# Hypnos_V0.net
KiCad netlist of a schematic drawn in EAGLE
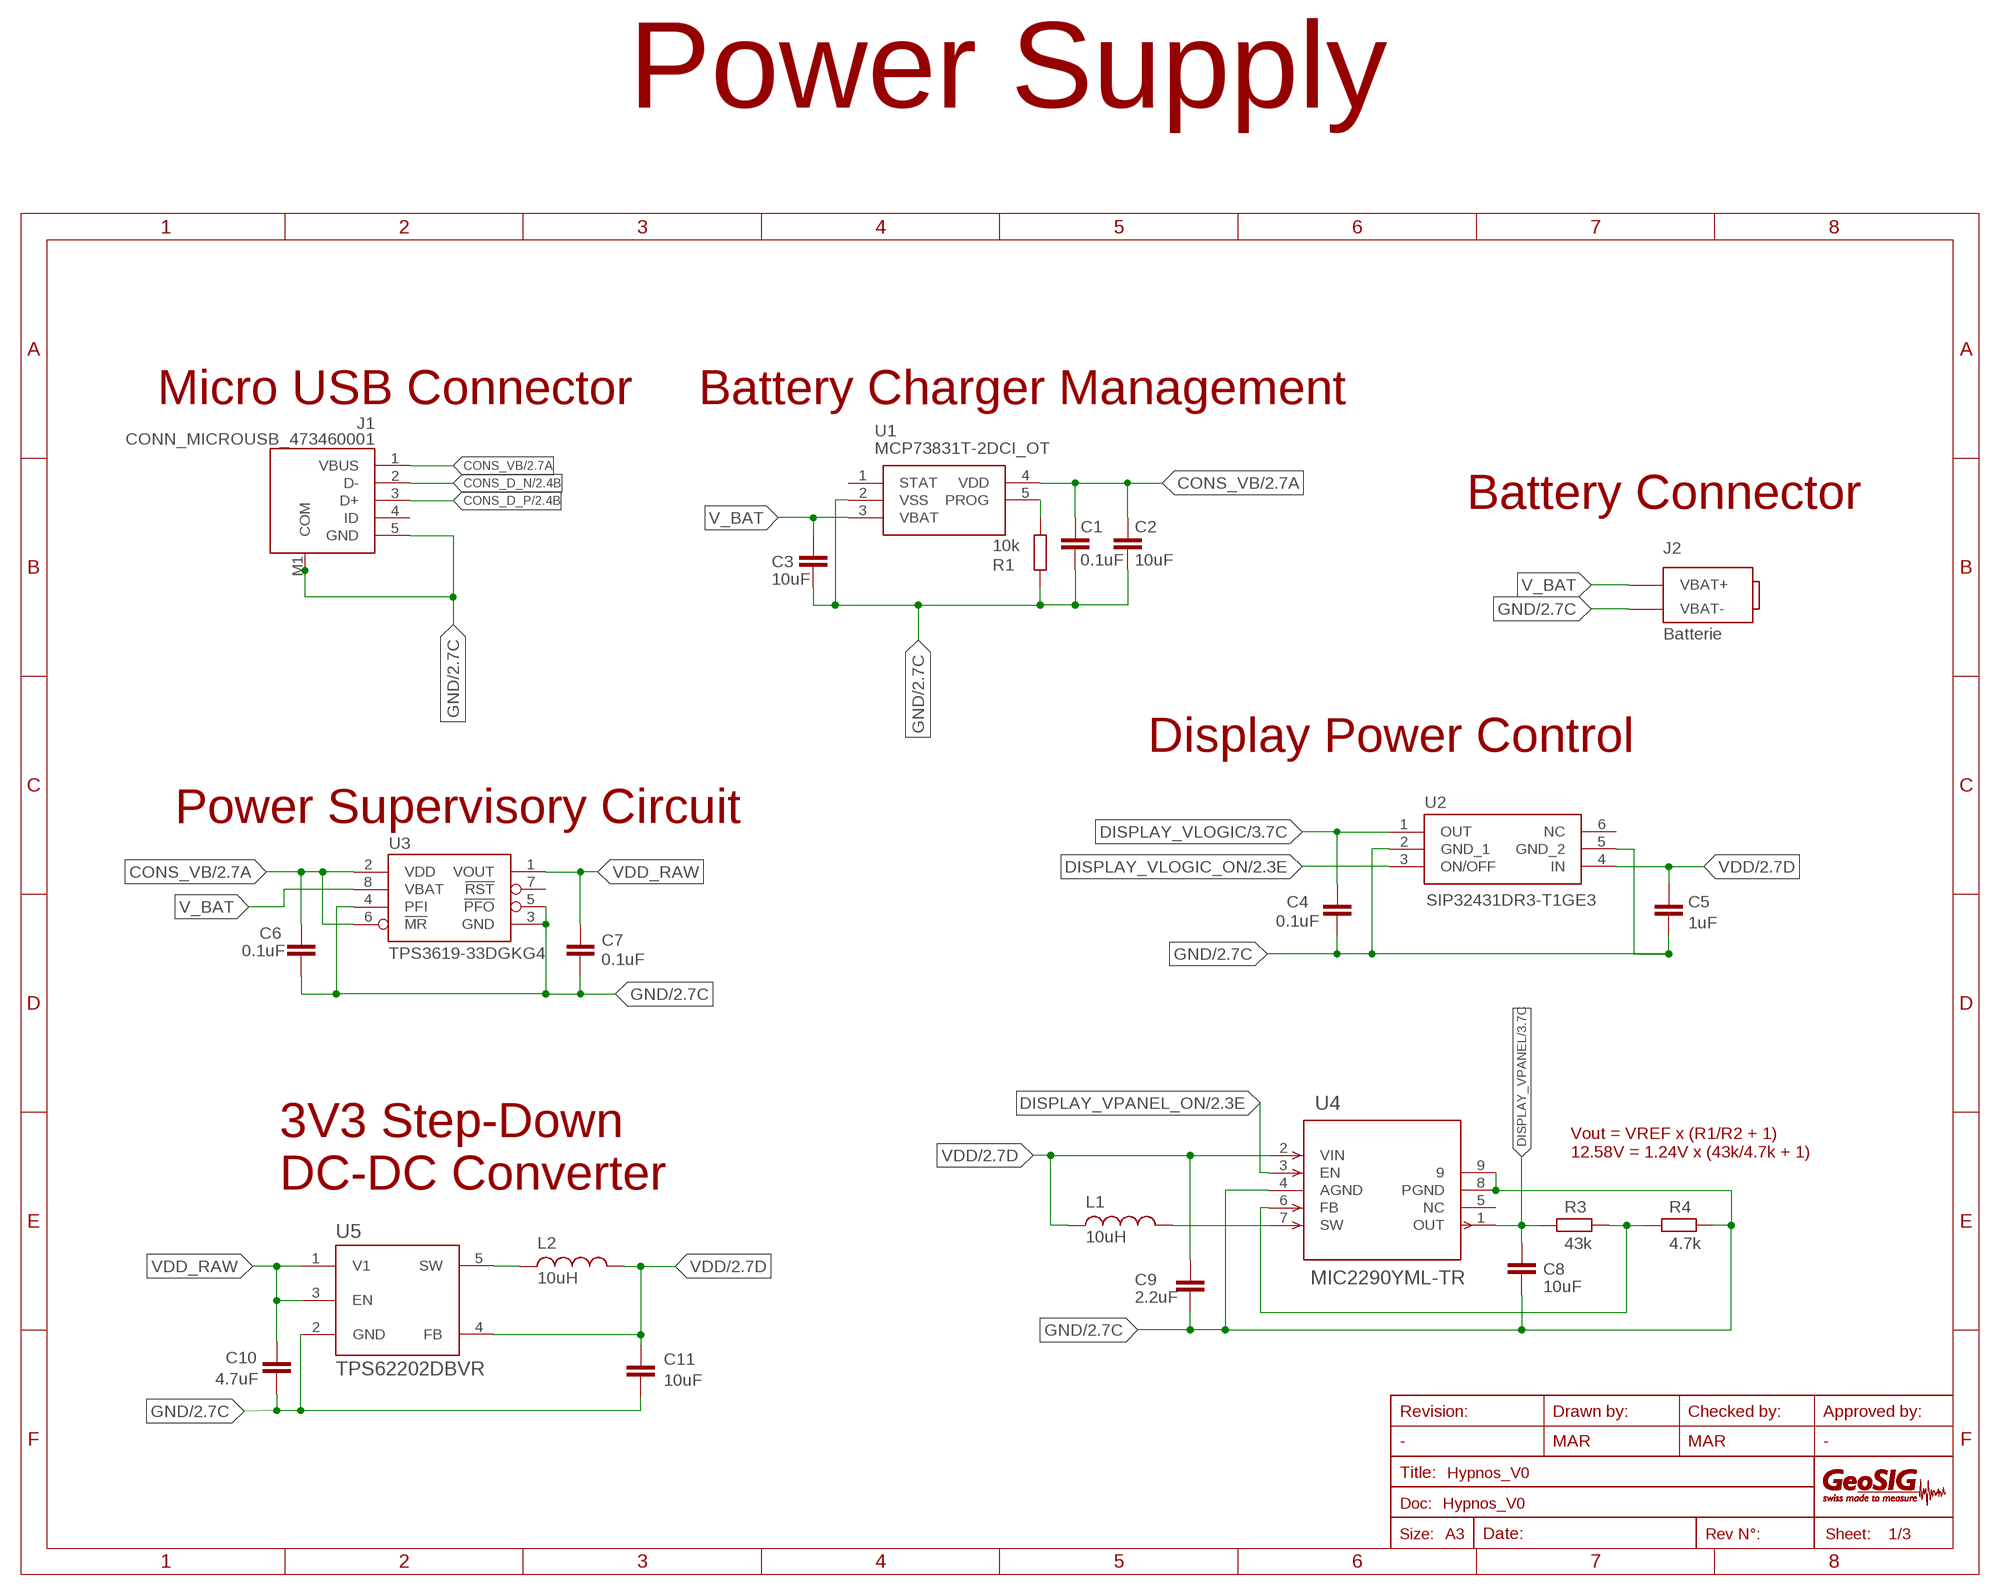
[diagram p0: schematic, sheet 1]
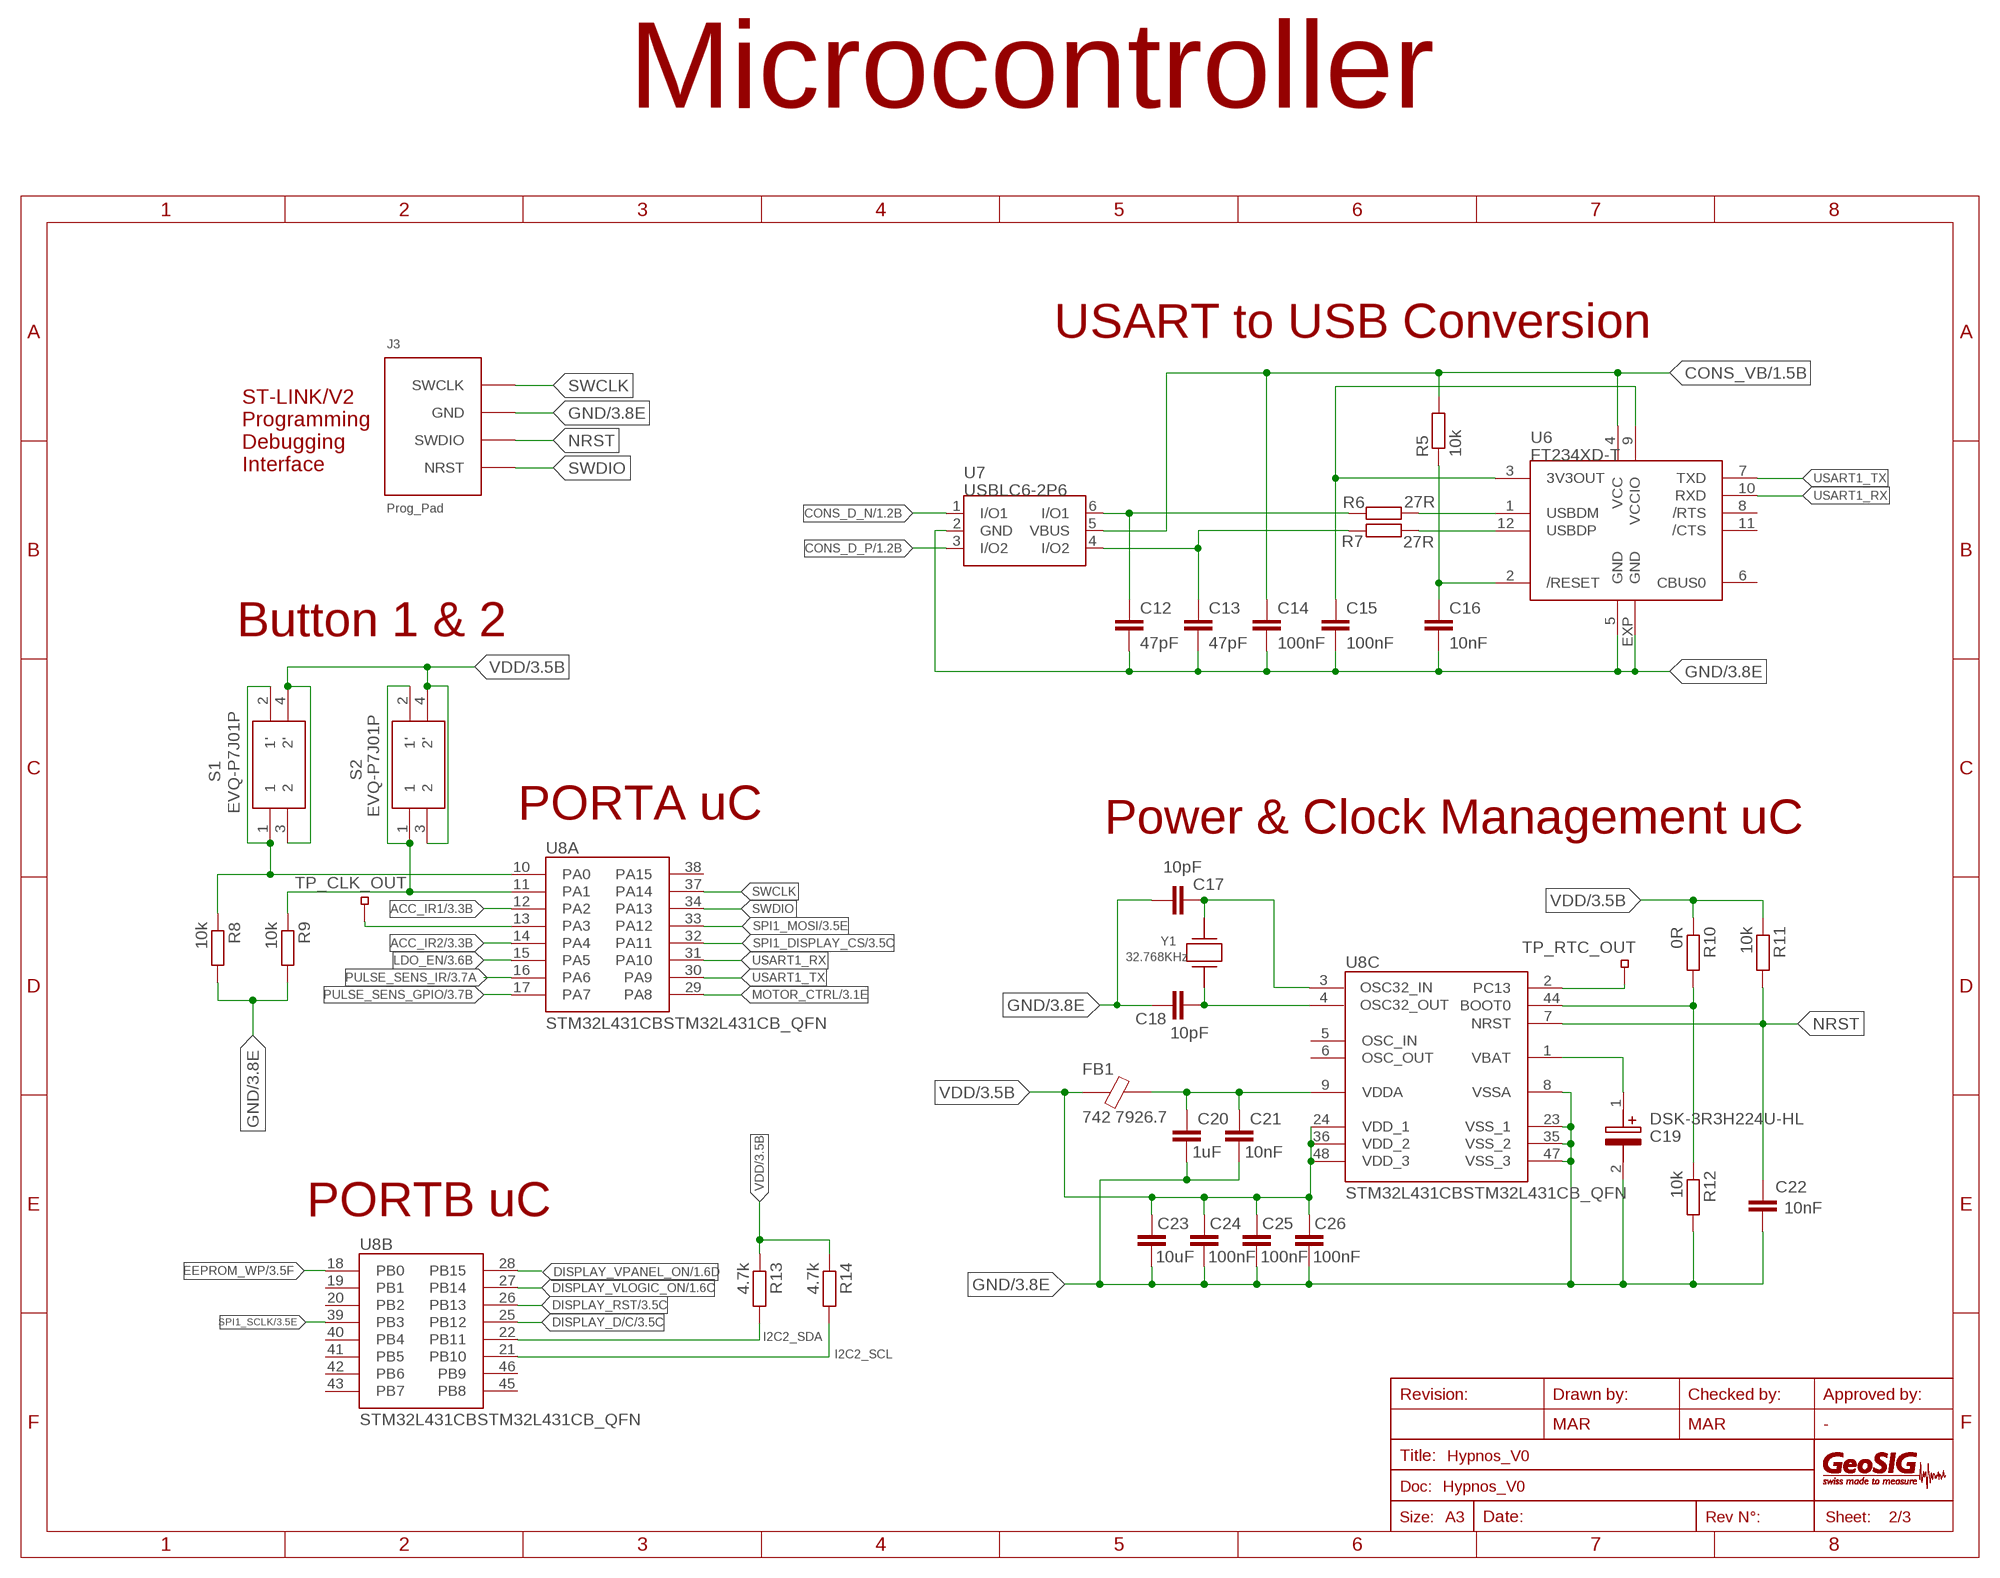
[diagram p1: schematic, sheet 2]
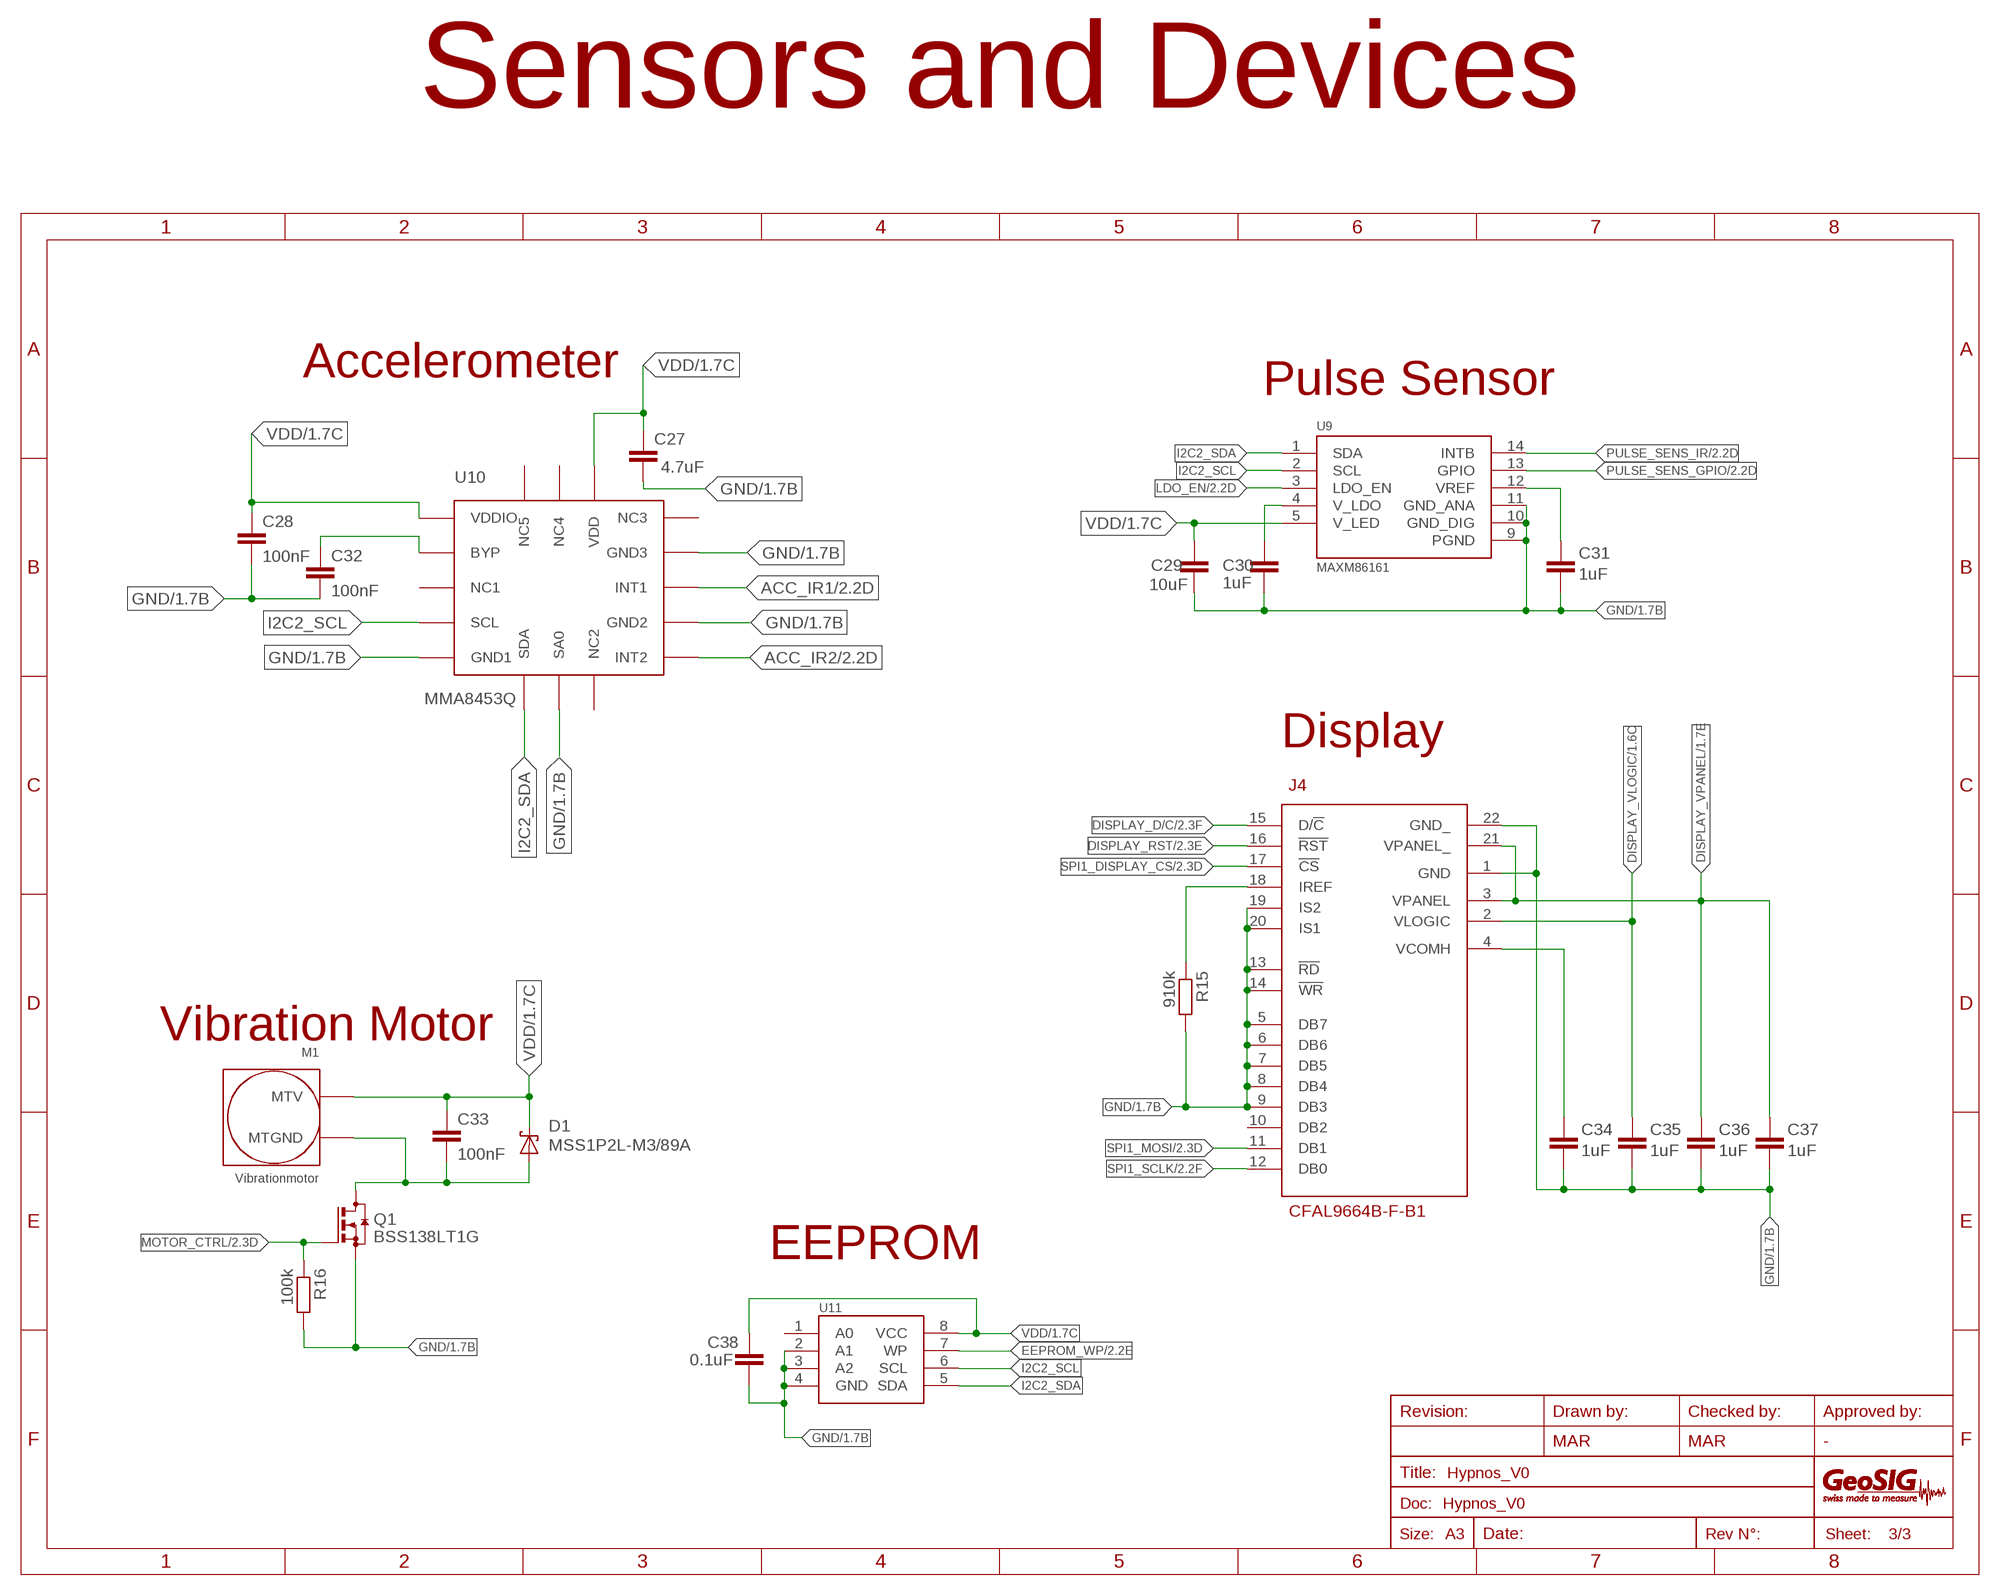
[diagram p2: schematic, sheet 3]

(export (version "E")
  (design (tool "Eeschema 10.0.6"))
  (components
    (comp (ref "C12")
      (value "47pF")
      (footprint "eagle-import:C0603K")
      (fields (field (name "MPN") "NONE"))
      (libsource (lib "eagle-import") (part "C0603"))
    )
    (comp (ref "C13")
      (value "47pF")
      (footprint "eagle-import:C0603K")
      (fields (field (name "MPN") "NONE"))
      (libsource (lib "eagle-import") (part "C0603"))
    )
    (comp (ref "C14")
      (value "100nF")
      (footprint "eagle-import:C0603K")
      (fields (field (name "MPN") "NONE"))
      (libsource (lib "eagle-import") (part "C0603"))
    )
    (comp (ref "C15")
      (value "100nF")
      (footprint "eagle-import:C0603K")
      (fields (field (name "MPN") "NONE"))
      (libsource (lib "eagle-import") (part "C0603"))
    )
    (comp (ref "C16")
      (value "10nF")
      (footprint "eagle-import:C0603K")
      (fields (field (name "MPN") "NONE"))
      (libsource (lib "eagle-import") (part "C0603"))
    )
    (comp (ref "C17")
      (value "10pF")
      (footprint "eagle-import:C0603K")
      (fields (field (name "MPN") "NONE"))
      (libsource (lib "eagle-import") (part "C0603"))
    )
    (comp (ref "C18")
      (value "10pF")
      (footprint "eagle-import:C0603K")
      (fields (field (name "MPN") "NONE"))
      (libsource (lib "eagle-import") (part "C0603"))
    )
    (comp (ref "C19")
      (value "DSK-3R3H224U-HL")
      (footprint "eagle-import:DSK3R3H334THL")
      (fields (field (name "MOUSER_PART_NUMBER") "555-DSK3R3H224U-HL"))
      (libsource (lib "eagle-import") (part "DSK-3R3H224U-HL"))
    )
    (comp (ref "C20")
      (value "1uF")
      (footprint "eagle-import:C0603K")
      (fields (field (name "MPN") "NONE"))
      (libsource (lib "eagle-import") (part "C0603"))
    )
    (comp (ref "C21")
      (value "10nF")
      (footprint "eagle-import:C0603K")
      (fields (field (name "MPN") "NONE"))
      (libsource (lib "eagle-import") (part "C0603"))
    )
    (comp (ref "C22")
      (value "10nF")
      (footprint "eagle-import:C0603K")
      (fields (field (name "MPN") "NONE"))
      (libsource (lib "eagle-import") (part "C0603"))
    )
    (comp (ref "C23")
      (value "10uF")
      (footprint "eagle-import:C0603K")
      (fields (field (name "MPN") "NONE"))
      (libsource (lib "eagle-import") (part "C0603"))
    )
    (comp (ref "C24")
      (value "100nF")
      (footprint "eagle-import:C0603K")
      (fields (field (name "MPN") "NONE"))
      (libsource (lib "eagle-import") (part "C0603"))
    )
    (comp (ref "C25")
      (value "100nF")
      (footprint "eagle-import:C0603K")
      (fields (field (name "MPN") "NONE"))
      (libsource (lib "eagle-import") (part "C0603"))
    )
    (comp (ref "C26")
      (value "100nF")
      (footprint "eagle-import:C0603K")
      (fields (field (name "MPN") "NONE"))
      (libsource (lib "eagle-import") (part "C0603"))
    )
    (comp (ref "FB1")
      (value "742 7926.7")
      (footprint "eagle-import:FB0603")
      (fields (field (name "MPN") "NONE"))
      (libsource (lib "eagle-import") (part "FERRITE_BEAD0603"))
    )
    (comp (ref "J3")
      (value "Prog_Pad")
      (footprint "eagle-import:PROG_PAD")
      (libsource (lib "eagle-import") (part "PROG_PAD"))
    )
    (comp (ref "R5")
      (value "10k")
      (footprint "eagle-import:R0603")
      (fields (field (name "MPN") "NONE"))
      (libsource (lib "eagle-import") (part "R-EU_R0603"))
    )
    (comp (ref "R6")
      (value "27R")
      (footprint "eagle-import:R0603")
      (fields (field (name "MPN") "NONE"))
      (libsource (lib "eagle-import") (part "R-EU_R0603"))
    )
    (comp (ref "R7")
      (value "27R")
      (footprint "eagle-import:R0603")
      (fields (field (name "MPN") "NONE"))
      (libsource (lib "eagle-import") (part "R-EU_R0603"))
    )
    (comp (ref "R8")
      (value "10k")
      (footprint "eagle-import:R0603")
      (fields (field (name "MPN") "NONE"))
      (libsource (lib "eagle-import") (part "R-EU_R0603"))
    )
    (comp (ref "R9")
      (value "10k")
      (footprint "eagle-import:R0603")
      (fields (field (name "MPN") "NONE"))
      (libsource (lib "eagle-import") (part "R-EU_R0603"))
    )
    (comp (ref "R10")
      (value "0R")
      (footprint "eagle-import:R0603")
      (fields (field (name "MPN") "NONE"))
      (libsource (lib "eagle-import") (part "R-EU_R0603"))
    )
    (comp (ref "R11")
      (value "10k")
      (footprint "eagle-import:R0603")
      (fields (field (name "MPN") "NONE"))
      (libsource (lib "eagle-import") (part "R-EU_R0603"))
    )
    (comp (ref "R12")
      (value "10k")
      (footprint "eagle-import:R0603")
      (fields (field (name "MPN") "NONE"))
      (libsource (lib "eagle-import") (part "R-EU_R0603"))
    )
    (comp (ref "R13")
      (value "4.7k")
      (footprint "eagle-import:R0603")
      (fields (field (name "MPN") "NONE"))
      (libsource (lib "eagle-import") (part "R-EU_R0603"))
    )
    (comp (ref "R14")
      (value "4.7k")
      (footprint "eagle-import:R0603")
      (fields (field (name "MPN") "NONE"))
      (libsource (lib "eagle-import") (part "R-EU_R0603"))
    )
    (comp (ref "S1")
      (value "EVQ-P7J01P")
      (footprint "eagle-import:EVQP7J01P")
      (fields (field (name "MOUSER_PART_NUMBER") "667-EVQP7J01P"))
      (libsource (lib "eagle-import") (part "EVQ-P7J01P"))
    )
    (comp (ref "S2")
      (value "EVQ-P7J01P")
      (footprint "eagle-import:EVQP7J01P")
      (fields (field (name "MOUSER_PART_NUMBER") "667-EVQP7J01P"))
      (libsource (lib "eagle-import") (part "EVQ-P7J01P"))
    )
    (comp (ref "TP_CLK_OUT")
      (value "TEST_PIN_SMD")
      (footprint "eagle-import:SMD_1")
      (fields (field (name "MPN") "NONE"))
      (libsource (lib "eagle-import") (part "TEST_PIN_SMD"))
    )
    (comp (ref "TP_RTC_OUT")
      (value "TEST_PIN_SMD")
      (footprint "eagle-import:SMD_1")
      (fields (field (name "MPN") "NONE"))
      (libsource (lib "eagle-import") (part "TEST_PIN_SMD"))
    )
    (comp (ref "U6")
      (value "FT234XD-T")
      (footprint "eagle-import:DFN12-3X3")
      (libsource (lib "eagle-import") (part "FT234XD-T"))
    )
    (comp (ref "U7")
      (value "USBLC6-2P6")
      (footprint "eagle-import:SOT666")
      (libsource (lib "eagle-import") (part "USBLC6-2P6"))
    )
    (comp (ref "U8")
      (value "STM32L431CBSTM32L431CB_QFN")
      (footprint "eagle-import:QFN50P700X700X60-49N")
      (libsource (lib "eagle-import") (part "STM32L431CBSTM32L431CB_QFN"))
    )
    (comp (ref "Y1")
      (value "32.768KHz")
      (footprint "eagle-import:CM315")
      (fields (field (name "MPN") "CM315-32.768KDZY-UT"))
      (libsource (lib "eagle-import") (part "QUARTZ1-CM315-32.768KDZY-UT"))
    )
    (comp (ref "C1")
      (value "0.1uF")
      (footprint "eagle-import:C0603K")
      (fields (field (name "MPN") "NONE"))
      (libsource (lib "eagle-import") (part "C0603"))
    )
    (comp (ref "C2")
      (value "10uF")
      (footprint "eagle-import:C0603K")
      (fields (field (name "MPN") "NONE"))
      (libsource (lib "eagle-import") (part "C0603"))
    )
    (comp (ref "C3")
      (value "10uF")
      (footprint "eagle-import:C0603K")
      (fields (field (name "MPN") "NONE"))
      (libsource (lib "eagle-import") (part "C0603"))
    )
    (comp (ref "C4")
      (value "0.1uF")
      (footprint "eagle-import:C0603K")
      (fields (field (name "MPN") "NONE"))
      (libsource (lib "eagle-import") (part "C0603"))
    )
    (comp (ref "C5")
      (value "1uF")
      (footprint "eagle-import:C0603K")
      (fields (field (name "MPN") "NONE"))
      (libsource (lib "eagle-import") (part "C0603"))
    )
    (comp (ref "C6")
      (value "0.1uF")
      (footprint "eagle-import:C0603K")
      (fields (field (name "MPN") "NONE"))
      (libsource (lib "eagle-import") (part "C0603"))
    )
    (comp (ref "C7")
      (value "0.1uF")
      (footprint "eagle-import:C0603K")
      (fields (field (name "MPN") "NONE"))
      (libsource (lib "eagle-import") (part "C0603"))
    )
    (comp (ref "C8")
      (value "10uF")
      (footprint "eagle-import:C0603K")
      (fields (field (name "MPN") "NONE"))
      (libsource (lib "eagle-import") (part "C0603"))
    )
    (comp (ref "C9")
      (value "2.2uF")
      (footprint "eagle-import:C0603K")
      (fields (field (name "MPN") "NONE"))
      (libsource (lib "eagle-import") (part "C0603"))
    )
    (comp (ref "C10")
      (value "4.7uF")
      (footprint "eagle-import:C0603K")
      (fields (field (name "MPN") "NONE"))
      (libsource (lib "eagle-import") (part "C0603"))
    )
    (comp (ref "C11")
      (value "10uF")
      (footprint "eagle-import:C0603K")
      (fields (field (name "MPN") "NONE"))
      (libsource (lib "eagle-import") (part "C0603"))
    )
    (comp (ref "J1")
      (value "CONN_MICROUSB_473460001")
      (footprint "eagle-import:CONN_MOLEX_473460001")
      (fields (field (name "MPN") "47346-0001"))
      (libsource (lib "eagle-import") (part "CONN_MICROUSB_473460001"))
    )
    (comp (ref "J2")
      (value "Batterie")
      (footprint "eagle-import:BATTERIE")
      (libsource (lib "eagle-import") (part "BATTERIE"))
    )
    (comp (ref "L1")
      (value "10uH")
      (footprint "eagle-import:L1210")
      (fields (field (name "MPN") "NONE"))
      (libsource (lib "eagle-import") (part "INDUCT1210"))
    )
    (comp (ref "L2")
      (value "10uH")
      (footprint "eagle-import:L1210")
      (fields (field (name "MPN") "NONE"))
      (libsource (lib "eagle-import") (part "INDUCT1210"))
    )
    (comp (ref "R1")
      (value "10k")
      (footprint "eagle-import:R0603")
      (fields (field (name "MPN") "NONE"))
      (libsource (lib "eagle-import") (part "R-EU_R0603"))
    )
    (comp (ref "R3")
      (value "43k")
      (footprint "eagle-import:R0603")
      (fields (field (name "MPN") "NONE"))
      (libsource (lib "eagle-import") (part "R-EU_R0603"))
    )
    (comp (ref "R4")
      (value "4.7k")
      (footprint "eagle-import:R0603")
      (fields (field (name "MPN") "NONE"))
      (libsource (lib "eagle-import") (part "R-EU_R0603"))
    )
    (comp (ref "U1")
      (value "MCP73831T-2DCI_OT")
      (footprint "eagle-import:SOT95P270X145-5N")
      (fields
        (field (name "MANUFACTURER_PART_NUMBER") "MCP73831T-2DCI/OT")
        (field (name "MOUSER_PART_NUMBER") "579-MCP73831T-2DCIOT")
      )
      (libsource (lib "eagle-import") (part "MCP73831T-2DCI_OT"))
    )
    (comp (ref "U2")
      (value "SIP32431DR3-T1GE3")
      (footprint "eagle-import:SOT65P210X110-6N")
      (fields (field (name "MOUSER_PART_NUMBER") "781-SIP32431DR3-GE3"))
      (libsource (lib "eagle-import") (part "SIP32431DR3-T1GE3"))
    )
    (comp (ref "U3")
      (value "TPS3619-33DGKG4")
      (footprint "eagle-import:MSOP8")
      (libsource (lib "eagle-import") (part "TPS3619-33DGKG4"))
    )
    (comp (ref "U4")
      (value "MIC2290YML-TR")
      (footprint "eagle-import:MLF-8_ML_MCH")
      (fields (field (name "COPYRIGHT") "Copyright (C) 2018 Accelerated Designs. All rights reserved"))
      (libsource (lib "eagle-import") (part "MIC2290YML-TR"))
    )
    (comp (ref "U5")
      (value "TPS62202DBVR")
      (footprint "eagle-import:SOT95P280X145-5N")
      (fields (field (name "MF") "Texas Instruments"))
      (libsource (lib "eagle-import") (part "TPS62202DBVR"))
    )
    (comp (ref "C27")
      (value "4.7uF")
      (footprint "eagle-import:C0603K")
      (fields (field (name "MPN") "NONE"))
      (libsource (lib "eagle-import") (part "C0603"))
    )
    (comp (ref "C28")
      (value "100nF")
      (footprint "eagle-import:C0603K")
      (fields (field (name "MPN") "NONE"))
      (libsource (lib "eagle-import") (part "C0603"))
    )
    (comp (ref "C29")
      (value "10uF")
      (footprint "eagle-import:C0603K")
      (fields (field (name "MPN") "NONE"))
      (libsource (lib "eagle-import") (part "C0603"))
    )
    (comp (ref "C30")
      (value "1uF")
      (footprint "eagle-import:C0603K")
      (fields (field (name "MPN") "NONE"))
      (libsource (lib "eagle-import") (part "C0603"))
    )
    (comp (ref "C31")
      (value "1uF")
      (footprint "eagle-import:C0603K")
      (fields (field (name "MPN") "NONE"))
      (libsource (lib "eagle-import") (part "C0603"))
    )
    (comp (ref "C32")
      (value "100nF")
      (footprint "eagle-import:C0603K")
      (fields (field (name "MPN") "NONE"))
      (libsource (lib "eagle-import") (part "C0603"))
    )
    (comp (ref "C33")
      (value "100nF")
      (footprint "eagle-import:C0603K")
      (fields (field (name "MPN") "NONE"))
      (libsource (lib "eagle-import") (part "C0603"))
    )
    (comp (ref "C34")
      (value "1uF")
      (footprint "eagle-import:C0603K")
      (fields (field (name "MPN") "NONE"))
      (libsource (lib "eagle-import") (part "C0603"))
    )
    (comp (ref "C35")
      (value "1uF")
      (footprint "eagle-import:C0603K")
      (fields (field (name "MPN") "NONE"))
      (libsource (lib "eagle-import") (part "C0603"))
    )
    (comp (ref "C36")
      (value "1uF")
      (footprint "eagle-import:C0603K")
      (fields (field (name "MPN") "NONE"))
      (libsource (lib "eagle-import") (part "C0603"))
    )
    (comp (ref "C37")
      (value "1uF")
      (footprint "eagle-import:C0603K")
      (fields (field (name "MPN") "NONE"))
      (libsource (lib "eagle-import") (part "C0603"))
    )
    (comp (ref "C38")
      (value "0.1uF")
      (footprint "eagle-import:C0603K")
      (fields (field (name "MPN") "NONE"))
      (libsource (lib "eagle-import") (part "C0603"))
    )
    (comp (ref "D1")
      (value "MSS1P2L-M3/89A")
      (footprint "eagle-import:MICROSMP")
      (libsource (lib "eagle-import") (part "MSS1P2L-M3/89A"))
    )
    (comp (ref "J4")
      (value "CFAL9664B-F-B1")
      (footprint "eagle-import:CFAL9664B-F-B1")
      (libsource (lib "eagle-import") (part "CFAL9664B-F-B1"))
    )
    (comp (ref "M1")
      (value "Vibrationmotor")
      (footprint "eagle-import:VIBRATIONMOTOR")
      (libsource (lib "eagle-import") (part "VIBRATIONMOTOR"))
    )
    (comp (ref "Q1")
      (value "BSS138LT1G")
      (footprint "eagle-import:SOT23")
      (libsource (lib "eagle-import") (part "BSS138LT1G"))
    )
    (comp (ref "R15")
      (value "910k")
      (footprint "eagle-import:R0603")
      (fields (field (name "MPN") "NONE"))
      (libsource (lib "eagle-import") (part "R-EU_R0603"))
    )
    (comp (ref "R16")
      (value "100k")
      (footprint "eagle-import:R0603")
      (fields (field (name "MPN") "NONE"))
      (libsource (lib "eagle-import") (part "R-EU_R0603"))
    )
    (comp (ref "U9")
      (value "MAXM86161")
      (footprint "eagle-import:MAXM86161")
      (fields (field (name "MF") "Maxim Integrated") (field (name "MP") "MAX30101EFD+"))
      (libsource (lib "eagle-import") (part "MAXM86161"))
    )
    (comp (ref "U10")
      (value "MMA8453Q")
      (footprint "eagle-import:QFN-COL")
      (fields (field (name "MF") "NXP Semiconductors"))
      (libsource (lib "eagle-import") (part "MMA8453Q"))
    )
    (comp (ref "U11")
      (value "BR24T1MFJ-3AME2")
      (footprint "eagle-import:SOIC127P600X165-8N")
      (libsource (lib "eagle-import") (part "BR24T1MFJ-3AME2"))
    )
  )
  (nets
    (net (code "1") (name "ACC_IR1") (class "Default")
      (node (ref "U10") (pin "P$11") (pinfunction "INT1_P$11") (pintype "bidirectional"))
      (node (ref "U8") (pin "12") (pinfunction "PA2_12") (pintype "bidirectional"))
    )
    (net (code "2") (name "ACC_IR2") (class "Default")
      (node (ref "U10") (pin "P$9") (pinfunction "INT2_P$9") (pintype "bidirectional"))
      (node (ref "U8") (pin "14") (pinfunction "PA4_14") (pintype "bidirectional"))
    )
    (net (code "3") (name "CONS_D_N") (class "Default")
      (node (ref "J1") (pin "2") (pinfunction "D-_2") (pintype "bidirectional"))
      (node (ref "U7") (pin "1") (pinfunction "I/O1_1") (pintype "bidirectional"))
    )
    (net (code "4") (name "CONS_D_P") (class "Default")
      (node (ref "J1") (pin "3") (pinfunction "D+_3") (pintype "bidirectional"))
      (node (ref "U7") (pin "3") (pinfunction "I/O2_3") (pintype "bidirectional"))
    )
    (net (code "5") (name "CONS_VB") (class "Default")
      (node (ref "C1") (pin "1") (pinfunction "1_1") (pintype "passive"))
      (node (ref "C14") (pin "1") (pinfunction "1_1") (pintype "passive"))
      (node (ref "C2") (pin "1") (pinfunction "1_1") (pintype "passive"))
      (node (ref "C6") (pin "1") (pinfunction "1_1") (pintype "passive"))
      (node (ref "J1") (pin "1") (pinfunction "VBUS_1") (pintype "power_in"))
      (node (ref "R5") (pin "2") (pinfunction "2_2") (pintype "passive"))
      (node (ref "U1") (pin "4") (pinfunction "VDD_4") (pintype "bidirectional"))
      (node (ref "U3") (pin "2") (pinfunction "VDD_2") (pintype "power_in"))
      (node (ref "U3") (pin "6") (pinfunction "~{MR}_6") (pintype "passive"))
      (node (ref "U6") (pin "4") (pinfunction "VCC_4") (pintype "power_in"))
      (node (ref "U7") (pin "5") (pinfunction "VBUS_5") (pintype "input"))
    )
    (net (code "6") (name "DISPLAY_D{slash}C") (class "Default")
      (node (ref "J4") (pin "15") (pinfunction "D/~{C}_15") (pintype "input"))
      (node (ref "U8") (pin "25") (pinfunction "PB12_25") (pintype "bidirectional"))
    )
    (net (code "7") (name "DISPLAY_RST") (class "Default")
      (node (ref "J4") (pin "16") (pinfunction "~{RST}_16") (pintype "input"))
      (node (ref "U8") (pin "26") (pinfunction "PB13_26") (pintype "bidirectional"))
    )
    (net (code "8") (name "DISPLAY_VLOGIC") (class "Default")
      (node (ref "C35") (pin "1") (pinfunction "1_1") (pintype "passive"))
      (node (ref "C4") (pin "1") (pinfunction "1_1") (pintype "passive"))
      (node (ref "J4") (pin "2") (pinfunction "VLOGIC_2") (pintype "power_in"))
      (node (ref "U2") (pin "1") (pinfunction "OUT_1") (pintype "bidirectional"))
    )
    (net (code "9") (name "DISPLAY_VLOGIC_ON") (class "Default")
      (node (ref "U2") (pin "3") (pinfunction "ON/OFF_3") (pintype "bidirectional"))
      (node (ref "U8") (pin "27") (pinfunction "PB14_27") (pintype "bidirectional"))
    )
    (net (code "10") (name "DISPLAY_VPANEL") (class "Default")
      (node (ref "C36") (pin "1") (pinfunction "1_1") (pintype "passive"))
      (node (ref "C37") (pin "1") (pinfunction "1_1") (pintype "passive"))
      (node (ref "C8") (pin "1") (pinfunction "1_1") (pintype "passive"))
      (node (ref "J4") (pin "21") (pinfunction "VPANEL__21") (pintype "power_in"))
      (node (ref "J4") (pin "3") (pinfunction "VPANEL_3") (pintype "power_in"))
      (node (ref "R3") (pin "2") (pinfunction "2_2") (pintype "passive"))
      (node (ref "U4") (pin "1") (pinfunction "OUT_1") (pintype "output"))
    )
    (net (code "11") (name "DISPLAY_VPANEL_ON") (class "Default")
      (node (ref "U4") (pin "3") (pinfunction "EN_3") (pintype "input"))
      (node (ref "U8") (pin "28") (pinfunction "PB15_28") (pintype "bidirectional"))
    )
    (net (code "12") (name "EEPROM_WP") (class "Default")
      (node (ref "U11") (pin "7") (pinfunction "WP_7") (pintype "input"))
      (node (ref "U8") (pin "18") (pinfunction "PB0_18") (pintype "bidirectional"))
    )
    (net (code "13") (name "GND") (class "Default")
      (node (ref "C1") (pin "2") (pinfunction "2_2") (pintype "passive"))
      (node (ref "C10") (pin "2") (pinfunction "2_2") (pintype "passive"))
      (node (ref "C11") (pin "2") (pinfunction "2_2") (pintype "passive"))
      (node (ref "C12") (pin "2") (pinfunction "2_2") (pintype "passive"))
      (node (ref "C13") (pin "2") (pinfunction "2_2") (pintype "passive"))
      (node (ref "C14") (pin "2") (pinfunction "2_2") (pintype "passive"))
      (node (ref "C15") (pin "2") (pinfunction "2_2") (pintype "passive"))
      (node (ref "C16") (pin "2") (pinfunction "2_2") (pintype "passive"))
      (node (ref "C17") (pin "2") (pinfunction "2_2") (pintype "passive"))
      (node (ref "C18") (pin "2") (pinfunction "2_2") (pintype "passive"))
      (node (ref "C19") (pin "2") (pinfunction "-_2") (pintype "bidirectional"))
      (node (ref "C2") (pin "2") (pinfunction "2_2") (pintype "passive"))
      (node (ref "C20") (pin "2") (pinfunction "2_2") (pintype "passive"))
      (node (ref "C21") (pin "2") (pinfunction "2_2") (pintype "passive"))
      (node (ref "C22") (pin "2") (pinfunction "2_2") (pintype "passive"))
      (node (ref "C23") (pin "2") (pinfunction "2_2") (pintype "passive"))
      (node (ref "C24") (pin "2") (pinfunction "2_2") (pintype "passive"))
      (node (ref "C25") (pin "2") (pinfunction "2_2") (pintype "passive"))
      (node (ref "C26") (pin "2") (pinfunction "2_2") (pintype "passive"))
      (node (ref "C27") (pin "2") (pinfunction "2_2") (pintype "passive"))
      (node (ref "C28") (pin "2") (pinfunction "2_2") (pintype "passive"))
      (node (ref "C29") (pin "2") (pinfunction "2_2") (pintype "passive"))
      (node (ref "C3") (pin "2") (pinfunction "2_2") (pintype "passive"))
      (node (ref "C30") (pin "2") (pinfunction "2_2") (pintype "passive"))
      (node (ref "C31") (pin "2") (pinfunction "2_2") (pintype "passive"))
      (node (ref "C32") (pin "2") (pinfunction "2_2") (pintype "passive"))
      (node (ref "C34") (pin "2") (pinfunction "2_2") (pintype "passive"))
      (node (ref "C35") (pin "2") (pinfunction "2_2") (pintype "passive"))
      (node (ref "C36") (pin "2") (pinfunction "2_2") (pintype "passive"))
      (node (ref "C37") (pin "2") (pinfunction "2_2") (pintype "passive"))
      (node (ref "C38") (pin "2") (pinfunction "2_2") (pintype "passive"))
      (node (ref "C4") (pin "2") (pinfunction "2_2") (pintype "passive"))
      (node (ref "C5") (pin "2") (pinfunction "2_2") (pintype "passive"))
      (node (ref "C6") (pin "2") (pinfunction "2_2") (pintype "passive"))
      (node (ref "C7") (pin "2") (pinfunction "2_2") (pintype "passive"))
      (node (ref "C8") (pin "2") (pinfunction "2_2") (pintype "passive"))
      (node (ref "C9") (pin "2") (pinfunction "2_2") (pintype "passive"))
      (node (ref "J1") (pin "5") (pinfunction "GND_5") (pintype "power_in"))
      (node (ref "J1") (pin "M1") (pinfunction "COM_M1") (pintype "passive"))
      (node (ref "J1") (pin "M2") (pinfunction "COM_M2") (pintype "passive"))
      (node (ref "J1") (pin "M3") (pinfunction "COM_M3") (pintype "passive"))
      (node (ref "J1") (pin "M4") (pinfunction "COM_M4") (pintype "passive"))
      (node (ref "J1") (pin "M5") (pinfunction "COM_M5") (pintype "passive"))
      (node (ref "J1") (pin "M6") (pinfunction "COM_M6") (pintype "passive"))
      (node (ref "J2") (pin "2") (pinfunction "VBAT-_2") (pintype "power_in"))
      (node (ref "J3") (pin "2") (pinfunction "GND_2") (pintype "bidirectional"))
      (node (ref "J4") (pin "1") (pinfunction "GND_1") (pintype "power_in"))
      (node (ref "J4") (pin "13") (pinfunction "~{RD}_13") (pintype "input"))
      (node (ref "J4") (pin "14") (pinfunction "~{WR}_14") (pintype "input"))
      (node (ref "J4") (pin "19") (pinfunction "IS2_19") (pintype "input"))
      (node (ref "J4") (pin "20") (pinfunction "IS1_20") (pintype "input"))
      (node (ref "J4") (pin "22") (pinfunction "GND__22") (pintype "power_in"))
      (node (ref "J4") (pin "5") (pinfunction "DB7_5") (pintype "bidirectional"))
      (node (ref "J4") (pin "6") (pinfunction "DB6_6") (pintype "bidirectional"))
      (node (ref "J4") (pin "7") (pinfunction "DB5_7") (pintype "bidirectional"))
      (node (ref "J4") (pin "8") (pinfunction "DB4_8") (pintype "bidirectional"))
      (node (ref "J4") (pin "9") (pinfunction "DB3_9") (pintype "bidirectional"))
      (node (ref "Q1") (pin "2") (pinfunction "S_2") (pintype "passive"))
      (node (ref "R1") (pin "2") (pinfunction "2_2") (pintype "passive"))
      (node (ref "R12") (pin "2") (pinfunction "2_2") (pintype "passive"))
      (node (ref "R15") (pin "2") (pinfunction "2_2") (pintype "passive"))
      (node (ref "R16") (pin "2") (pinfunction "2_2") (pintype "passive"))
      (node (ref "R4") (pin "1") (pinfunction "1_1") (pintype "passive"))
      (node (ref "R8") (pin "2") (pinfunction "2_2") (pintype "passive"))
      (node (ref "R9") (pin "2") (pinfunction "2_2") (pintype "passive"))
      (node (ref "U1") (pin "2") (pinfunction "VSS_2") (pintype "bidirectional"))
      (node (ref "U10") (pin "P$10") (pinfunction "GND2_P$10") (pintype "bidirectional"))
      (node (ref "U10") (pin "P$12") (pinfunction "GND3_P$12") (pintype "bidirectional"))
      (node (ref "U10") (pin "P$5") (pinfunction "GND1_P$5") (pintype "bidirectional"))
      (node (ref "U10") (pin "P$7") (pinfunction "SA0_P$7") (pintype "bidirectional"))
      (node (ref "U11") (pin "2") (pinfunction "A1_2") (pintype "input"))
      (node (ref "U11") (pin "3") (pinfunction "A2_3") (pintype "input"))
      (node (ref "U11") (pin "4") (pinfunction "GND_4") (pintype "power_in"))
      (node (ref "U2") (pin "2") (pinfunction "GND_1_2") (pintype "bidirectional"))
      (node (ref "U2") (pin "5") (pinfunction "GND_2_5") (pintype "bidirectional"))
      (node (ref "U3") (pin "3") (pinfunction "GND_3") (pintype "power_in"))
      (node (ref "U3") (pin "4") (pinfunction "PFI_4") (pintype "power_in"))
      (node (ref "U3") (pin "5") (pinfunction "~{PFO}_5") (pintype "passive"))
      (node (ref "U4") (pin "4") (pinfunction "AGND_4") (pintype "power_in"))
      (node (ref "U4") (pin "8") (pinfunction "PGND_8") (pintype "power_in"))
      (node (ref "U4") (pin "9") (pinfunction "9_9") (pintype "passive"))
      (node (ref "U5") (pin "2") (pinfunction "GND_2") (pintype "passive"))
      (node (ref "U6") (pin "5") (pinfunction "GND_5") (pintype "power_in"))
      (node (ref "U6") (pin "EXP") (pinfunction "GND_EXP") (pintype "power_in"))
      (node (ref "U7") (pin "2") (pinfunction "GND_2") (pintype "input"))
      (node (ref "U8") (pin "23") (pinfunction "VSS_1_23") (pintype "power_in"))
      (node (ref "U8") (pin "35") (pinfunction "VSS_2_35") (pintype "power_in"))
      (node (ref "U8") (pin "47") (pinfunction "VSS_3_47") (pintype "power_in"))
      (node (ref "U8") (pin "8") (pinfunction "VSSA_8") (pintype "power_in"))
      (node (ref "U9") (pin "10") (pinfunction "GND_DIG_10") (pintype "power_in"))
      (node (ref "U9") (pin "11") (pinfunction "GND_ANA_11") (pintype "power_in"))
      (node (ref "U9") (pin "9") (pinfunction "PGND_9") (pintype "power_in"))
    )
    (net (code "14") (name "I2C2_SCL") (class "Default")
      (node (ref "R14") (pin "2") (pinfunction "2_2") (pintype "passive"))
      (node (ref "U10") (pin "P$4") (pinfunction "SCL_P$4") (pintype "bidirectional"))
      (node (ref "U11") (pin "6") (pinfunction "SCL_6") (pintype "bidirectional"))
      (node (ref "U8") (pin "21") (pinfunction "PB10_21") (pintype "bidirectional"))
      (node (ref "U9") (pin "2") (pinfunction "SCL_2") (pintype "bidirectional"))
    )
    (net (code "15") (name "I2C2_SDA") (class "Default")
      (node (ref "R13") (pin "2") (pinfunction "2_2") (pintype "passive"))
      (node (ref "U10") (pin "P$6") (pinfunction "SDA_P$6") (pintype "bidirectional"))
      (node (ref "U11") (pin "5") (pinfunction "SDA_5") (pintype "bidirectional"))
      (node (ref "U8") (pin "22") (pinfunction "PB11_22") (pintype "bidirectional"))
      (node (ref "U9") (pin "1") (pinfunction "SDA_1") (pintype "bidirectional"))
    )
    (net (code "16") (name "LDO_EN") (class "Default")
      (node (ref "U8") (pin "15") (pinfunction "PA5_15") (pintype "bidirectional"))
      (node (ref "U9") (pin "3") (pinfunction "LDO_EN_3") (pintype "input"))
    )
    (net (code "17") (name "MOTOR_CTRL") (class "Default")
      (node (ref "Q1") (pin "1") (pinfunction "G_1") (pintype "passive"))
      (node (ref "R16") (pin "1") (pinfunction "1_1") (pintype "passive"))
      (node (ref "U8") (pin "29") (pinfunction "PA8_29") (pintype "bidirectional"))
    )
    (net (code "18") (name "NRST") (class "Default")
      (node (ref "C22") (pin "1") (pinfunction "1_1") (pintype "passive"))
      (node (ref "J3") (pin "3") (pinfunction "SWDIO_3") (pintype "bidirectional"))
      (node (ref "R11") (pin "2") (pinfunction "2_2") (pintype "passive"))
      (node (ref "U8") (pin "7") (pinfunction "NRST_7") (pintype "bidirectional"))
    )
    (net (code "19") (name "Net-(C12-Pad1)") (class "Default")
      (node (ref "C12") (pin "1") (pinfunction "1_1") (pintype "passive"))
      (node (ref "R6") (pin "2") (pinfunction "2_2") (pintype "passive"))
      (node (ref "U7") (pin "6") (pinfunction "I/O1_6") (pintype "bidirectional"))
    )
    (net (code "20") (name "Net-(C13-Pad1)") (class "Default")
      (node (ref "C13") (pin "1") (pinfunction "1_1") (pintype "passive"))
      (node (ref "R7") (pin "2") (pinfunction "2_2") (pintype "passive"))
      (node (ref "U7") (pin "4") (pinfunction "I/O2_4") (pintype "bidirectional"))
    )
    (net (code "21") (name "Net-(C19-+)") (class "Default")
      (node (ref "C19") (pin "1") (pinfunction "+_1") (pintype "bidirectional"))
      (node (ref "U8") (pin "1") (pinfunction "VBAT_1") (pintype "bidirectional"))
    )
    (net (code "22") (name "Net-(FB1-P$2)") (class "Default")
      (node (ref "C20") (pin "1") (pinfunction "1_1") (pintype "passive"))
      (node (ref "C21") (pin "1") (pinfunction "1_1") (pintype "passive"))
      (node (ref "FB1") (pin "2") (pinfunction "P$2_2") (pintype "passive"))
      (node (ref "U8") (pin "9") (pinfunction "VDDA_9") (pintype "power_in"))
    )
    (net (code "23") (name "Net-(J4-IREF)") (class "Default")
      (node (ref "J4") (pin "18") (pinfunction "IREF_18") (pintype "output"))
      (node (ref "R15") (pin "1") (pinfunction "1_1") (pintype "passive"))
    )
    (net (code "24") (name "Net-(J4-VCOMH)") (class "Default")
      (node (ref "C34") (pin "1") (pinfunction "1_1") (pintype "passive"))
      (node (ref "J4") (pin "4") (pinfunction "VCOMH_4") (pintype "output"))
    )
    (net (code "25") (name "Net-(L1-P$2)") (class "Default")
      (node (ref "L1") (pin "2") (pinfunction "P$2_2") (pintype "passive"))
      (node (ref "U4") (pin "7") (pinfunction "SW_7") (pintype "input"))
    )
    (net (code "26") (name "Net-(L2-P$1)") (class "Default")
      (node (ref "L2") (pin "1") (pinfunction "P$1_1") (pintype "passive"))
      (node (ref "U5") (pin "5") (pinfunction "SW_5") (pintype "output"))
    )
    (net (code "27") (name "Net-(M1-MTGND)") (class "Default")
      (node (ref "C33") (pin "2") (pinfunction "2_2") (pintype "passive"))
      (node (ref "D1") (pin "A") (pinfunction "A_A") (pintype "passive"))
      (node (ref "M1") (pin "1") (pinfunction "MTGND_1") (pintype "bidirectional"))
      (node (ref "Q1") (pin "3") (pinfunction "D_3") (pintype "passive"))
    )
    (net (code "28") (name "Net-(S1-1')") (class "Default")
      (node (ref "R8") (pin "1") (pinfunction "1_1") (pintype "passive"))
      (node (ref "S1") (pin "1") (pinfunction "1_1") (pintype "bidirectional"))
      (node (ref "S1") (pin "2") (pinfunction "1'_2") (pintype "bidirectional"))
      (node (ref "U8") (pin "10") (pinfunction "PA0_10") (pintype "bidirectional"))
    )
    (net (code "29") (name "Net-(S2-1')") (class "Default")
      (node (ref "R9") (pin "1") (pinfunction "1_1") (pintype "passive"))
      (node (ref "S2") (pin "1") (pinfunction "1_1") (pintype "bidirectional"))
      (node (ref "S2") (pin "2") (pinfunction "1'_2") (pintype "bidirectional"))
      (node (ref "U8") (pin "11") (pinfunction "PA1_11") (pintype "bidirectional"))
    )
    (net (code "30") (name "Net-(TP_CLK_OUT-1)") (class "Default")
      (node (ref "TP_CLK_OUT") (pin "P$1") (pinfunction "1_P$1") (pintype "passive"))
      (node (ref "U8") (pin "13") (pinfunction "PA3_13") (pintype "bidirectional"))
    )
    (net (code "31") (name "Net-(TP_RTC_OUT-1)") (class "Default")
      (node (ref "TP_RTC_OUT") (pin "P$1") (pinfunction "1_P$1") (pintype "passive"))
      (node (ref "U8") (pin "2") (pinfunction "PC13_2") (pintype "bidirectional"))
    )
    (net (code "32") (name "Net-(U1-PROG)") (class "Default")
      (node (ref "R1") (pin "1") (pinfunction "1_1") (pintype "passive"))
      (node (ref "U1") (pin "5") (pinfunction "PROG_5") (pintype "bidirectional"))
    )
    (net (code "33") (name "Net-(U4-FB)") (class "Default")
      (node (ref "R3") (pin "1") (pinfunction "1_1") (pintype "passive"))
      (node (ref "R4") (pin "2") (pinfunction "2_2") (pintype "passive"))
      (node (ref "U4") (pin "6") (pinfunction "FB_6") (pintype "input"))
    )
    (net (code "34") (name "Net-(U6-3V3OUT)") (class "Default")
      (node (ref "C15") (pin "1") (pinfunction "1_1") (pintype "passive"))
      (node (ref "U6") (pin "3") (pinfunction "3V3OUT_3") (pintype "output"))
      (node (ref "U6") (pin "9") (pinfunction "VCCIO_9") (pintype "power_in"))
    )
    (net (code "35") (name "Net-(U6-USBDM)") (class "Default")
      (node (ref "R6") (pin "1") (pinfunction "1_1") (pintype "passive"))
      (node (ref "U6") (pin "1") (pinfunction "USBDM_1") (pintype "bidirectional"))
    )
    (net (code "36") (name "Net-(U6-USBDP)") (class "Default")
      (node (ref "R7") (pin "1") (pinfunction "1_1") (pintype "passive"))
      (node (ref "U6") (pin "12") (pinfunction "USBDP_12") (pintype "bidirectional"))
    )
    (net (code "37") (name "Net-(U6-{slash}RESET)") (class "Default")
      (node (ref "C16") (pin "1") (pinfunction "1_1") (pintype "passive"))
      (node (ref "R5") (pin "1") (pinfunction "1_1") (pintype "passive"))
      (node (ref "U6") (pin "2") (pinfunction "/RESET_2") (pintype "input"))
    )
    (net (code "38") (name "Net-(U8C-BOOT0)") (class "Default")
      (node (ref "R10") (pin "2") (pinfunction "2_2") (pintype "passive"))
      (node (ref "R12") (pin "1") (pinfunction "1_1") (pintype "passive"))
      (node (ref "U8") (pin "44") (pinfunction "BOOT0_44") (pintype "bidirectional"))
    )
    (net (code "39") (name "Net-(U8C-OSC32_IN)") (class "Default")
      (node (ref "C17") (pin "1") (pinfunction "1_1") (pintype "passive"))
      (node (ref "U8") (pin "3") (pinfunction "OSC32_IN_3") (pintype "bidirectional"))
      (node (ref "Y1") (pin "P$1") (pinfunction "P$1_P$1") (pintype "passive"))
    )
    (net (code "40") (name "Net-(U8C-OSC32_OUT)") (class "Default")
      (node (ref "C18") (pin "1") (pinfunction "1_1") (pintype "passive"))
      (node (ref "U8") (pin "4") (pinfunction "OSC32_OUT_4") (pintype "bidirectional"))
      (node (ref "Y1") (pin "P$2") (pinfunction "P$2_P$2") (pintype "passive"))
    )
    (net (code "41") (name "Net-(U9-VREF)") (class "Default")
      (node (ref "C31") (pin "1") (pinfunction "1_1") (pintype "passive"))
      (node (ref "U9") (pin "12") (pinfunction "VREF_12") (pintype "power_in"))
    )
    (net (code "42") (name "Net-(U9-V_LDO)") (class "Default")
      (node (ref "C30") (pin "1") (pinfunction "1_1") (pintype "passive"))
      (node (ref "U9") (pin "4") (pinfunction "V_LDO_4") (pintype "power_in"))
    )
    (net (code "43") (name "Net-(U10-BYP)") (class "Default")
      (node (ref "C32") (pin "1") (pinfunction "1_1") (pintype "passive"))
      (node (ref "U10") (pin "P$2") (pinfunction "BYP_P$2") (pintype "bidirectional"))
    )
    (net (code "44") (name "PULSE_SENS_GPIO") (class "Default")
      (node (ref "U8") (pin "17") (pinfunction "PA7_17") (pintype "bidirectional"))
      (node (ref "U9") (pin "13") (pinfunction "GPIO_13") (pintype "bidirectional"))
    )
    (net (code "45") (name "PULSE_SENS_IR") (class "Default")
      (node (ref "U8") (pin "16") (pinfunction "PA6_16") (pintype "bidirectional"))
      (node (ref "U9") (pin "14") (pinfunction "INTB_14") (pintype "output"))
    )
    (net (code "46") (name "SPI1_DISPLAY_CS") (class "Default")
      (node (ref "J4") (pin "17") (pinfunction "~{CS}_17") (pintype "input"))
      (node (ref "U8") (pin "32") (pinfunction "PA11_32") (pintype "bidirectional"))
    )
    (net (code "47") (name "SPI1_MOSI") (class "Default")
      (node (ref "J4") (pin "11") (pinfunction "DB1_11") (pintype "bidirectional"))
      (node (ref "U8") (pin "33") (pinfunction "PA12_33") (pintype "bidirectional"))
    )
    (net (code "48") (name "SPI1_SCLK") (class "Default")
      (node (ref "J4") (pin "12") (pinfunction "DB0_12") (pintype "input"))
      (node (ref "U8") (pin "39") (pinfunction "PB3_39") (pintype "bidirectional"))
    )
    (net (code "49") (name "SWCLK") (class "Default")
      (node (ref "J3") (pin "1") (pinfunction "SWCLK_1") (pintype "bidirectional"))
      (node (ref "U8") (pin "37") (pinfunction "PA14_37") (pintype "bidirectional"))
    )
    (net (code "50") (name "SWDIO") (class "Default")
      (node (ref "J3") (pin "4") (pinfunction "NRST_4") (pintype "bidirectional"))
      (node (ref "U8") (pin "34") (pinfunction "PA13_34") (pintype "bidirectional"))
    )
    (net (code "51") (name "USART1_RX") (class "Default")
      (node (ref "U6") (pin "10") (pinfunction "RXD_10") (pintype "input"))
      (node (ref "U8") (pin "31") (pinfunction "PA10_31") (pintype "bidirectional"))
    )
    (net (code "52") (name "USART1_TX") (class "Default")
      (node (ref "U6") (pin "7") (pinfunction "TXD_7") (pintype "output"))
      (node (ref "U8") (pin "30") (pinfunction "PA9_30") (pintype "bidirectional"))
    )
    (net (code "53") (name "VDD") (class "Default")
      (node (ref "C11") (pin "1") (pinfunction "1_1") (pintype "passive"))
      (node (ref "C23") (pin "1") (pinfunction "1_1") (pintype "passive"))
      (node (ref "C24") (pin "1") (pinfunction "1_1") (pintype "passive"))
      (node (ref "C25") (pin "1") (pinfunction "1_1") (pintype "passive"))
      (node (ref "C26") (pin "1") (pinfunction "1_1") (pintype "passive"))
      (node (ref "C27") (pin "1") (pinfunction "1_1") (pintype "passive"))
      (node (ref "C28") (pin "1") (pinfunction "1_1") (pintype "passive"))
      (node (ref "C29") (pin "1") (pinfunction "1_1") (pintype "passive"))
      (node (ref "C33") (pin "1") (pinfunction "1_1") (pintype "passive"))
      (node (ref "C38") (pin "1") (pinfunction "1_1") (pintype "passive"))
      (node (ref "C5") (pin "1") (pinfunction "1_1") (pintype "passive"))
      (node (ref "C9") (pin "1") (pinfunction "1_1") (pintype "passive"))
      (node (ref "D1") (pin "C") (pinfunction "C_C") (pintype "passive"))
      (node (ref "FB1") (pin "1") (pinfunction "P$1_1") (pintype "passive"))
      (node (ref "L1") (pin "1") (pinfunction "P$1_1") (pintype "passive"))
      (node (ref "L2") (pin "2") (pinfunction "P$2_2") (pintype "passive"))
      (node (ref "M1") (pin "2") (pinfunction "MTV_2") (pintype "bidirectional"))
      (node (ref "R10") (pin "1") (pinfunction "1_1") (pintype "passive"))
      (node (ref "R11") (pin "1") (pinfunction "1_1") (pintype "passive"))
      (node (ref "R13") (pin "1") (pinfunction "1_1") (pintype "passive"))
      (node (ref "R14") (pin "1") (pinfunction "1_1") (pintype "passive"))
      (node (ref "S1") (pin "3") (pinfunction "2_3") (pintype "bidirectional"))
      (node (ref "S1") (pin "4") (pinfunction "2'_4") (pintype "bidirectional"))
      (node (ref "S2") (pin "3") (pinfunction "2_3") (pintype "bidirectional"))
      (node (ref "S2") (pin "4") (pinfunction "2'_4") (pintype "bidirectional"))
      (node (ref "U10") (pin "P$1") (pinfunction "VDDIO_P$1") (pintype "bidirectional"))
      (node (ref "U10") (pin "P$14") (pinfunction "VDD_P$14") (pintype "bidirectional"))
      (node (ref "U11") (pin "8") (pinfunction "VCC_8") (pintype "power_in"))
      (node (ref "U2") (pin "4") (pinfunction "IN_4") (pintype "bidirectional"))
      (node (ref "U4") (pin "2") (pinfunction "VIN_2") (pintype "input"))
      (node (ref "U5") (pin "4") (pinfunction "FB_4") (pintype "input"))
      (node (ref "U8") (pin "24") (pinfunction "VDD_1_24") (pintype "power_in"))
      (node (ref "U8") (pin "36") (pinfunction "VDD_2_36") (pintype "power_in"))
      (node (ref "U8") (pin "48") (pinfunction "VDD_3_48") (pintype "power_in"))
      (node (ref "U9") (pin "5") (pinfunction "V_LED_5") (pintype "power_in"))
    )
    (net (code "54") (name "VDD_RAW") (class "Default")
      (node (ref "C10") (pin "1") (pinfunction "1_1") (pintype "passive"))
      (node (ref "C7") (pin "1") (pinfunction "1_1") (pintype "passive"))
      (node (ref "U3") (pin "1") (pinfunction "VOUT_1") (pintype "output"))
      (node (ref "U5") (pin "1") (pinfunction "V1_1") (pintype "power_in"))
      (node (ref "U5") (pin "3") (pinfunction "EN_3") (pintype "input"))
    )
    (net (code "55") (name "V_BAT") (class "Default")
      (node (ref "C3") (pin "1") (pinfunction "1_1") (pintype "passive"))
      (node (ref "J2") (pin "1") (pinfunction "VBAT+_1") (pintype "power_in"))
      (node (ref "U1") (pin "3") (pinfunction "VBAT_3") (pintype "bidirectional"))
      (node (ref "U3") (pin "8") (pinfunction "VBAT_8") (pintype "passive"))
    )
    (net (code "56") (name "unconnected-(J1-ID-Pad4)") (class "Default")
      (node (ref "J1") (pin "4") (pinfunction "ID_4") (pintype "no_connect"))
    )
    (net (code "57") (name "unconnected-(J4-DB2-Pad10)") (class "Default")
      (node (ref "J4") (pin "10") (pinfunction "DB2_10") (pintype "bidirectional"))
    )
    (net (code "58") (name "unconnected-(U1-STAT-Pad1)") (class "Default")
      (node (ref "U1") (pin "1") (pinfunction "STAT_1") (pintype "bidirectional"))
    )
    (net (code "59") (name "unconnected-(U2-NC-Pad6)") (class "Default")
      (node (ref "U2") (pin "6") (pinfunction "NC_6") (pintype "no_connect"))
    )
    (net (code "60") (name "unconnected-(U3-~{RST}-Pad7)") (class "Default")
      (node (ref "U3") (pin "7") (pinfunction "~{RST}_7") (pintype "passive"))
    )
    (net (code "61") (name "unconnected-(U4-NC-Pad5)") (class "Default")
      (node (ref "U4") (pin "5") (pinfunction "NC_5") (pintype "no_connect"))
    )
    (net (code "62") (name "unconnected-(U6-CBUS0-Pad6)") (class "Default")
      (node (ref "U6") (pin "6") (pinfunction "CBUS0_6") (pintype "bidirectional"))
    )
    (net (code "63") (name "unconnected-(U6-{slash}CTS-Pad11)") (class "Default")
      (node (ref "U6") (pin "11") (pinfunction "/CTS_11") (pintype "input"))
    )
    (net (code "64") (name "unconnected-(U6-{slash}RTS-Pad8)") (class "Default")
      (node (ref "U6") (pin "8") (pinfunction "/RTS_8") (pintype "output"))
    )
    (net (code "65") (name "unconnected-(U8A-PA15-Pad38)") (class "Default")
      (node (ref "U8") (pin "38") (pinfunction "PA15_38") (pintype "bidirectional"))
    )
    (net (code "66") (name "unconnected-(U8B-PB1-Pad19)") (class "Default")
      (node (ref "U8") (pin "19") (pinfunction "PB1_19") (pintype "bidirectional"))
    )
    (net (code "67") (name "unconnected-(U8B-PB2-Pad20)") (class "Default")
      (node (ref "U8") (pin "20") (pinfunction "PB2_20") (pintype "bidirectional"))
    )
    (net (code "68") (name "unconnected-(U8B-PB4-Pad40)") (class "Default")
      (node (ref "U8") (pin "40") (pinfunction "PB4_40") (pintype "bidirectional"))
    )
    (net (code "69") (name "unconnected-(U8B-PB5-Pad41)") (class "Default")
      (node (ref "U8") (pin "41") (pinfunction "PB5_41") (pintype "bidirectional"))
    )
    (net (code "70") (name "unconnected-(U8B-PB6-Pad42)") (class "Default")
      (node (ref "U8") (pin "42") (pinfunction "PB6_42") (pintype "bidirectional"))
    )
    (net (code "71") (name "unconnected-(U8B-PB7-Pad43)") (class "Default")
      (node (ref "U8") (pin "43") (pinfunction "PB7_43") (pintype "bidirectional"))
    )
    (net (code "72") (name "unconnected-(U8B-PB8-Pad45)") (class "Default")
      (node (ref "U8") (pin "45") (pinfunction "PB8_45") (pintype "bidirectional"))
    )
    (net (code "73") (name "unconnected-(U8B-PB9-Pad46)") (class "Default")
      (node (ref "U8") (pin "46") (pinfunction "PB9_46") (pintype "bidirectional"))
    )
    (net (code "74") (name "unconnected-(U8C-OSC_IN-Pad5)") (class "Default")
      (node (ref "U8") (pin "5") (pinfunction "OSC_IN_5") (pintype "bidirectional"))
    )
    (net (code "75") (name "unconnected-(U8C-OSC_OUT-Pad6)") (class "Default")
      (node (ref "U8") (pin "6") (pinfunction "OSC_OUT_6") (pintype "bidirectional"))
    )
    (net (code "76") (name "unconnected-(U10-NC1-PadP$3)") (class "Default")
      (node (ref "U10") (pin "P$3") (pinfunction "NC1_P$3") (pintype "bidirectional"))
    )
    (net (code "77") (name "unconnected-(U10-NC2-PadP$8)") (class "Default")
      (node (ref "U10") (pin "P$8") (pinfunction "NC2_P$8") (pintype "bidirectional"))
    )
    (net (code "78") (name "unconnected-(U10-NC3-PadP$13)") (class "Default")
      (node (ref "U10") (pin "P$13") (pinfunction "NC3_P$13") (pintype "bidirectional"))
    )
    (net (code "79") (name "unconnected-(U10-NC4-PadP$15)") (class "Default")
      (node (ref "U10") (pin "P$15") (pinfunction "NC4_P$15") (pintype "bidirectional"))
    )
    (net (code "80") (name "unconnected-(U10-NC5-PadP$16)") (class "Default")
      (node (ref "U10") (pin "P$16") (pinfunction "NC5_P$16") (pintype "bidirectional"))
    )
    (net (code "81") (name "unconnected-(U11-A0-Pad1)") (class "Default")
      (node (ref "U11") (pin "1") (pinfunction "A0_1") (pintype "tri_state"))
    )
  )
)
